# multi-pcb-_base.net
KiCad netlist of a schematic drawn in EAGLE
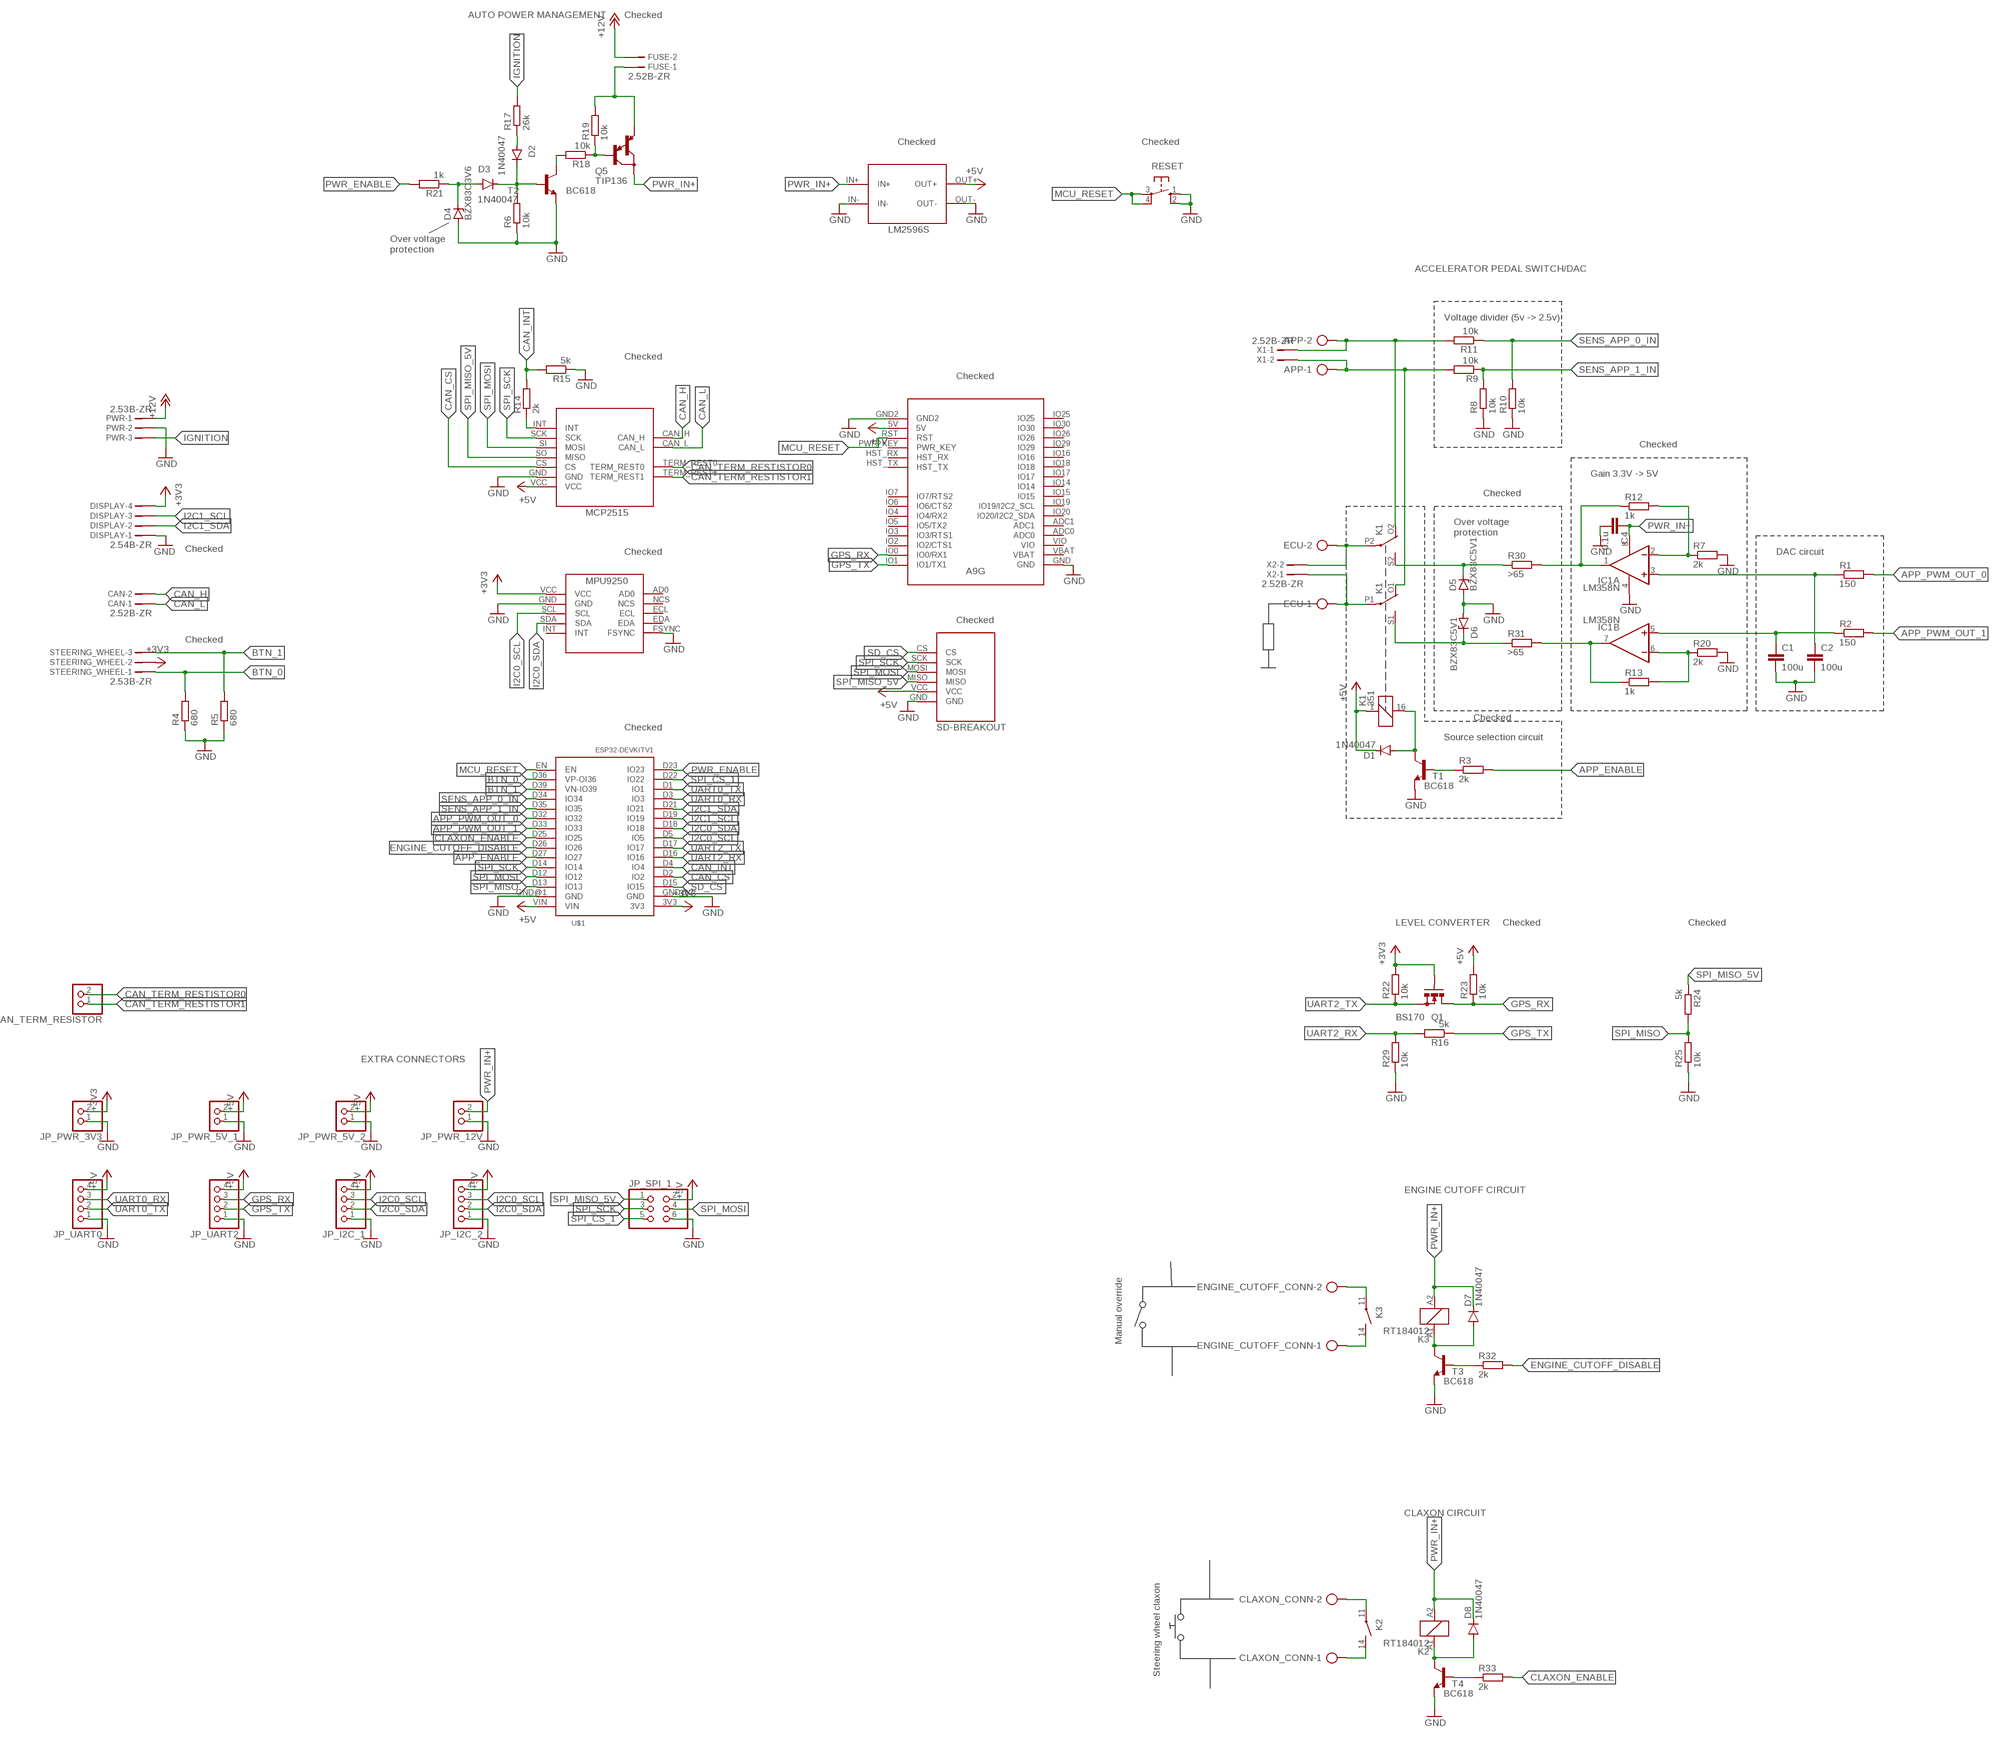
[diagram p0: schematic, sheet 1]

(export (version "E")
  (design (tool "Eeschema 10.0.6"))
  (components
    (comp (ref "APP")
      (value "AK300/2")
      (footprint "eagle-import:AK300_2")
      (libsource (lib "eagle-import") (part "AK300/2"))
    )
    (comp (ref "C1")
      (value "100u")
      (footprint "eagle-import:C025-050X050")
      (libsource (lib "eagle-import") (part "C-EU025-050X050"))
    )
    (comp (ref "C2")
      (value "100u")
      (footprint "eagle-import:C025-050X050")
      (libsource (lib "eagle-import") (part "C-EU025-050X050"))
    )
    (comp (ref "C4")
      (value "0.1u")
      (footprint "eagle-import:C025-050X050")
      (libsource (lib "eagle-import") (part "C-EU025-050X050"))
    )
    (comp (ref "CAN")
      (value "2.52B-ZR")
      (footprint "eagle-import:B2B-ZR2.5")
      (libsource (lib "eagle-import") (part "?2B-ZR2.5"))
    )
    (comp (ref "CAN_TERM_RESISTOR")
      (value "PINHD-1X2")
      (footprint "eagle-import:1X02")
      (libsource (lib "eagle-import") (part "PINHD-1X2"))
    )
    (comp (ref "CLAXON_CONN")
      (value "AK300/2")
      (footprint "eagle-import:AK300_2")
      (libsource (lib "eagle-import") (part "AK300/2"))
    )
    (comp (ref "D1")
      (value "1N40047")
      (footprint "eagle-import:DO41-7.6")
      (libsource (lib "eagle-import") (part "1N40047"))
    )
    (comp (ref "D2")
      (value "1N40047")
      (footprint "eagle-import:DO41-7.6")
      (libsource (lib "eagle-import") (part "1N40047"))
    )
    (comp (ref "D3")
      (value "1N40047")
      (footprint "eagle-import:DO41-7.6")
      (libsource (lib "eagle-import") (part "1N40047"))
    )
    (comp (ref "D4")
      (value "BZX83C3V6")
      (footprint "eagle-import:DO41Z7.6")
      (libsource (lib "eagle-import") (part "BZX857"))
    )
    (comp (ref "D5")
      (value "BZX83C5V1")
      (footprint "eagle-import:DO41Z7.6")
      (libsource (lib "eagle-import") (part "BZX857"))
    )
    (comp (ref "D6")
      (value "BZX83C5V1")
      (footprint "eagle-import:DO41Z7.6")
      (libsource (lib "eagle-import") (part "BZX857"))
    )
    (comp (ref "D7")
      (value "1N40047")
      (footprint "eagle-import:DO41-7.6")
      (libsource (lib "eagle-import") (part "1N40047"))
    )
    (comp (ref "D8")
      (value "1N40047")
      (footprint "eagle-import:DO41-7.6")
      (libsource (lib "eagle-import") (part "1N40047"))
    )
    (comp (ref "DISPLAY")
      (value "2.54B-ZR")
      (footprint "eagle-import:B4B-ZR2.5")
      (libsource (lib "eagle-import") (part "?4B-ZR2.5"))
    )
    (comp (ref "ECU")
      (value "AK300/2")
      (footprint "eagle-import:AK300_2")
      (libsource (lib "eagle-import") (part "AK300/2"))
    )
    (comp (ref "ENGINE_CUTOFF_CONN")
      (value "AK300/2")
      (footprint "eagle-import:AK300_2")
      (libsource (lib "eagle-import") (part "AK300/2"))
    )
    (comp (ref "FUSE")
      (value "2.52B-ZR")
      (footprint "eagle-import:B2B-ZR2.5")
      (libsource (lib "eagle-import") (part "?2B-ZR2.5"))
    )
    (comp (ref "IC1")
      (value "LM358N")
      (footprint "eagle-import:DIL08")
      (libsource (lib "eagle-import") (part "LM358N"))
    )
    (comp (ref "JP_I2C_1")
      (value "PINHD-1X4")
      (footprint "eagle-import:1X04")
      (libsource (lib "eagle-import") (part "PINHD-1X4"))
    )
    (comp (ref "JP_I2C_2")
      (value "PINHD-1X4")
      (footprint "eagle-import:1X04")
      (libsource (lib "eagle-import") (part "PINHD-1X4"))
    )
    (comp (ref "JP_PWR_3V3")
      (value "PINHD-1X2")
      (footprint "eagle-import:1X02")
      (libsource (lib "eagle-import") (part "PINHD-1X2"))
    )
    (comp (ref "JP_PWR_5V_1")
      (value "PINHD-1X2")
      (footprint "eagle-import:1X02")
      (libsource (lib "eagle-import") (part "PINHD-1X2"))
    )
    (comp (ref "JP_PWR_5V_2")
      (value "PINHD-1X2")
      (footprint "eagle-import:1X02")
      (libsource (lib "eagle-import") (part "PINHD-1X2"))
    )
    (comp (ref "JP_PWR_12V")
      (value "PINHD-1X2")
      (footprint "eagle-import:1X02")
      (libsource (lib "eagle-import") (part "PINHD-1X2"))
    )
    (comp (ref "JP_SPI_1")
      (value "PINHD-2X3")
      (footprint "eagle-import:2X03")
      (libsource (lib "eagle-import") (part "PINHD-2X3"))
    )
    (comp (ref "JP_UART0")
      (value "PINHD-1X4")
      (footprint "eagle-import:1X04")
      (libsource (lib "eagle-import") (part "PINHD-1X4"))
    )
    (comp (ref "JP_UART2")
      (value "PINHD-1X4")
      (footprint "eagle-import:1X04")
      (libsource (lib "eagle-import") (part "PINHD-1X4"))
    )
    (comp (ref "K1")
      (value "351")
      (footprint "eagle-import:351")
      (libsource (lib "eagle-import") (part "351"))
    )
    (comp (ref "K2")
      (value "RT184012")
      (footprint "eagle-import:RT-N_O12A3.5")
      (fields (field (name "MF") "TYCO ELECTRONICS"))
      (libsource (lib "eagle-import") (part "RT?184012"))
    )
    (comp (ref "K3")
      (value "RT184012")
      (footprint "eagle-import:RT-N_O12A3.5")
      (fields (field (name "MF") "TYCO ELECTRONICS"))
      (libsource (lib "eagle-import") (part "RT?184012"))
    )
    (comp (ref "PWR")
      (value "2.53B-ZR")
      (footprint "eagle-import:B3B-ZR2.5")
      (libsource (lib "eagle-import") (part "?3B-ZR2.5"))
    )
    (comp (ref "Q1")
      (value "BS170")
      (footprint "eagle-import:SOT54E")
      (libsource (lib "eagle-import") (part "BS170"))
    )
    (comp (ref "Q5")
      (value "TIP136")
      (footprint "eagle-import:TO220")
      (libsource (lib "eagle-import") (part "TIP136"))
    )
    (comp (ref "R1")
      (value "150")
      (footprint "eagle-import:0309_10")
      (libsource (lib "eagle-import") (part "R-EU_0309/10"))
    )
    (comp (ref "R2")
      (value "150")
      (footprint "eagle-import:0309_10")
      (libsource (lib "eagle-import") (part "R-EU_0309/10"))
    )
    (comp (ref "R3")
      (value "2k")
      (footprint "eagle-import:0207_7")
      (libsource (lib "eagle-import") (part "R-EU_0207/7"))
    )
    (comp (ref "R4")
      (value "680")
      (footprint "eagle-import:0207_7")
      (libsource (lib "eagle-import") (part "R-EU_0207/7"))
    )
    (comp (ref "R5")
      (value "680")
      (footprint "eagle-import:0207_7")
      (libsource (lib "eagle-import") (part "R-EU_0207/7"))
    )
    (comp (ref "R6")
      (value "10k")
      (footprint "eagle-import:0207_7")
      (libsource (lib "eagle-import") (part "R-EU_0207/7"))
    )
    (comp (ref "R7")
      (value "2k")
      (footprint "eagle-import:0207_7")
      (libsource (lib "eagle-import") (part "R-EU_0207/7"))
    )
    (comp (ref "R8")
      (value "10k")
      (footprint "eagle-import:0207_7")
      (libsource (lib "eagle-import") (part "R-EU_0207/7"))
    )
    (comp (ref "R9")
      (value "10k")
      (footprint "eagle-import:0309_10")
      (libsource (lib "eagle-import") (part "R-EU_0309/10"))
    )
    (comp (ref "R10")
      (value "10k")
      (footprint "eagle-import:0207_7")
      (libsource (lib "eagle-import") (part "R-EU_0207/7"))
    )
    (comp (ref "R11")
      (value "10k")
      (footprint "eagle-import:0309_10")
      (libsource (lib "eagle-import") (part "R-EU_0309/10"))
    )
    (comp (ref "R12")
      (value "1k")
      (footprint "eagle-import:0207_7")
      (libsource (lib "eagle-import") (part "R-EU_0207/7"))
    )
    (comp (ref "R13")
      (value "1k")
      (footprint "eagle-import:0207_7")
      (libsource (lib "eagle-import") (part "R-EU_0207/7"))
    )
    (comp (ref "R14")
      (value "2k")
      (footprint "eagle-import:0309_10")
      (libsource (lib "eagle-import") (part "R-EU_0309/10"))
    )
    (comp (ref "R15")
      (value "5k")
      (footprint "eagle-import:0207_7")
      (libsource (lib "eagle-import") (part "R-EU_0207/7"))
    )
    (comp (ref "R16")
      (value "5k")
      (footprint "eagle-import:0207_7")
      (libsource (lib "eagle-import") (part "R-EU_0207/7"))
    )
    (comp (ref "R17")
      (value "26k")
      (footprint "eagle-import:0207_7")
      (libsource (lib "eagle-import") (part "R-EU_0207/7"))
    )
    (comp (ref "R18")
      (value "10k")
      (footprint "eagle-import:0207_7")
      (libsource (lib "eagle-import") (part "R-EU_0207/7"))
    )
    (comp (ref "R19")
      (value "10k")
      (footprint "eagle-import:0207_7")
      (libsource (lib "eagle-import") (part "R-EU_0207/7"))
    )
    (comp (ref "R20")
      (value "2k")
      (footprint "eagle-import:0207_7")
      (libsource (lib "eagle-import") (part "R-EU_0207/7"))
    )
    (comp (ref "R21")
      (value "1k")
      (footprint "eagle-import:0309_10")
      (libsource (lib "eagle-import") (part "R-EU_0309/10"))
    )
    (comp (ref "R22")
      (value "10k")
      (footprint "eagle-import:0207_7")
      (libsource (lib "eagle-import") (part "R-EU_0207/7"))
    )
    (comp (ref "R23")
      (value "10k")
      (footprint "eagle-import:0207_7")
      (libsource (lib "eagle-import") (part "R-EU_0207/7"))
    )
    (comp (ref "R24")
      (value "5k")
      (footprint "eagle-import:0207_7")
      (libsource (lib "eagle-import") (part "R-EU_0207/7"))
    )
    (comp (ref "R25")
      (value "10k")
      (footprint "eagle-import:0207_7")
      (libsource (lib "eagle-import") (part "R-EU_0207/7"))
    )
    (comp (ref "R29")
      (value "10k")
      (footprint "eagle-import:0207_7")
      (libsource (lib "eagle-import") (part "R-EU_0207/7"))
    )
    (comp (ref "R30")
      (value ">65")
      (footprint "eagle-import:0207_7")
      (libsource (lib "eagle-import") (part "R-EU_0207/7"))
    )
    (comp (ref "R31")
      (value ">65")
      (footprint "eagle-import:0207_7")
      (libsource (lib "eagle-import") (part "R-EU_0207/7"))
    )
    (comp (ref "R32")
      (value "2k")
      (footprint "eagle-import:0309_10")
      (libsource (lib "eagle-import") (part "R-EU_0309/10"))
    )
    (comp (ref "R33")
      (value "2k")
      (footprint "eagle-import:0309_10")
      (libsource (lib "eagle-import") (part "R-EU_0309/10"))
    )
    (comp (ref "RESET")
      (value "10-XX")
      (footprint "eagle-import:B3F-10XX")
      (fields (field (name "MPN") "B3F-1000"))
      (libsource (lib "eagle-import") (part "10-XX"))
    )
    (comp (ref "STEERING_WHEEL")
      (value "2.53B-ZR")
      (footprint "eagle-import:B3B-ZR2.5")
      (libsource (lib "eagle-import") (part "?3B-ZR2.5"))
    )
    (comp (ref "T1")
      (value "BC618")
      (footprint "eagle-import:TO92-EBC")
      (libsource (lib "eagle-import") (part "BC618"))
    )
    (comp (ref "T2")
      (value "BC618")
      (footprint "eagle-import:TO92-EBC")
      (libsource (lib "eagle-import") (part "BC618"))
    )
    (comp (ref "T3")
      (value "BC618")
      (footprint "eagle-import:TO92-EBC")
      (libsource (lib "eagle-import") (part "BC618"))
    )
    (comp (ref "T4")
      (value "BC618")
      (footprint "eagle-import:TO92-EBC")
      (libsource (lib "eagle-import") (part "BC618"))
    )
    (comp (ref "U$1")
      (value "ESP32DEVKITV1")
      (footprint "eagle-import:ESP32-DEVKITV1")
      (libsource (lib "eagle-import") (part "ESP32DEVKITV1"))
    )
    (comp (ref "U$2")
      (value "MCP2515_DEVBOARDINVERTED")
      (footprint "eagle-import:MCP2515_DEVBOARD_INVERTED")
      (libsource (lib "eagle-import") (part "MCP2515_DEVBOARDINVERTED"))
    )
    (comp (ref "U$3")
      (value "MPU9250_BREAKOUT")
      (footprint "eagle-import:MPU9250_BREAKOUT")
      (libsource (lib "eagle-import") (part "MPU9250_BREAKOUT"))
    )
    (comp (ref "U$4")
      (value "LM2596S")
      (footprint "eagle-import:LM2596S")
      (libsource (lib "eagle-import") (part "LM2596S"))
    )
    (comp (ref "U$5")
      (value "HKD-MICRO-SD-BREAKOUTH")
      (footprint "eagle-import:HKD-MICRO-SD-BREAKOUT")
      (libsource (lib "eagle-import") (part "HKD-MICRO-SD-BREAKOUTH"))
    )
    (comp (ref "U$6")
      (value "A9G")
      (footprint "eagle-import:A9G")
      (libsource (lib "eagle-import") (part "A9G"))
    )
    (comp (ref "X1")
      (value "2.52B-ZR")
      (footprint "eagle-import:B2B-ZR2.5")
      (libsource (lib "eagle-import") (part "?2B-ZR2.5"))
    )
    (comp (ref "X2")
      (value "2.52B-ZR")
      (footprint "eagle-import:B2B-ZR2.5")
      (libsource (lib "eagle-import") (part "?2B-ZR2.5"))
    )
  )
  (nets
    (net (code "1") (name "+3V3") (class "Default")
      (node (ref "DISPLAY") (pin "4") (pinfunction "1_4") (pintype "passive"))
      (node (ref "JP_PWR_3V3") (pin "2") (pinfunction "2_2") (pintype "passive"))
      (node (ref "Q1") (pin "G") (pinfunction "G_G") (pintype "passive"))
      (node (ref "R22") (pin "2") (pinfunction "2_2") (pintype "passive"))
      (node (ref "STEERING_WHEEL") (pin "2") (pinfunction "1_2") (pintype "passive"))
      (node (ref "U$1") (pin "3V3") (pinfunction "3V3_3V3") (pintype "bidirectional"))
      (node (ref "U$3") (pin "VCC") (pinfunction "VCC_VCC") (pintype "bidirectional"))
    )
    (net (code "2") (name "+5V") (class "Default")
      (node (ref "D1") (pin "C") (pinfunction "C_C") (pintype "passive"))
      (node (ref "JP_I2C_1") (pin "4") (pinfunction "4_4") (pintype "passive"))
      (node (ref "JP_I2C_2") (pin "4") (pinfunction "4_4") (pintype "passive"))
      (node (ref "JP_PWR_5V_1") (pin "2") (pinfunction "2_2") (pintype "passive"))
      (node (ref "JP_PWR_5V_2") (pin "2") (pinfunction "2_2") (pintype "passive"))
      (node (ref "JP_SPI_1") (pin "2") (pinfunction "2_2") (pintype "passive"))
      (node (ref "JP_UART0") (pin "4") (pinfunction "4_4") (pintype "passive"))
      (node (ref "JP_UART2") (pin "4") (pinfunction "4_4") (pintype "passive"))
      (node (ref "K1") (pin "1") (pinfunction "1_1") (pintype "passive"))
      (node (ref "R23") (pin "2") (pinfunction "2_2") (pintype "passive"))
      (node (ref "U$1") (pin "VIN") (pinfunction "VIN_VIN") (pintype "bidirectional"))
      (node (ref "U$2") (pin "VCC") (pinfunction "VCC_VCC") (pintype "bidirectional"))
      (node (ref "U$4") (pin "OUT+") (pinfunction "OUT+_OUT+") (pintype "bidirectional"))
      (node (ref "U$5") (pin "VCC") (pinfunction "VCC_VCC") (pintype "bidirectional"))
      (node (ref "U$6") (pin "5V") (pinfunction "5V_5V") (pintype "bidirectional"))
    )
    (net (code "3") (name "+12V") (class "Default")
      (node (ref "FUSE") (pin "2") (pinfunction "1_2") (pintype "passive"))
      (node (ref "PWR") (pin "1") (pinfunction "1_1") (pintype "passive"))
    )
    (net (code "4") (name "APP_ENABLE") (class "Default")
      (node (ref "R3") (pin "2") (pinfunction "2_2") (pintype "passive"))
      (node (ref "U$1") (pin "D27") (pinfunction "IO27_D27") (pintype "bidirectional"))
    )
    (net (code "5") (name "APP_PWM_OUT_0") (class "Default")
      (node (ref "R1") (pin "2") (pinfunction "2_2") (pintype "passive"))
      (node (ref "U$1") (pin "D32") (pinfunction "IO32_D32") (pintype "bidirectional"))
    )
    (net (code "6") (name "APP_PWM_OUT_1") (class "Default")
      (node (ref "R2") (pin "2") (pinfunction "2_2") (pintype "passive"))
      (node (ref "U$1") (pin "D33") (pinfunction "IO33_D33") (pintype "bidirectional"))
    )
    (net (code "7") (name "BTN_0") (class "Default")
      (node (ref "R4") (pin "2") (pinfunction "2_2") (pintype "passive"))
      (node (ref "STEERING_WHEEL") (pin "1") (pinfunction "1_1") (pintype "passive"))
      (node (ref "U$1") (pin "D36") (pinfunction "VP-OI36_D36") (pintype "bidirectional"))
    )
    (net (code "8") (name "BTN_1") (class "Default")
      (node (ref "R5") (pin "2") (pinfunction "2_2") (pintype "passive"))
      (node (ref "STEERING_WHEEL") (pin "3") (pinfunction "1_3") (pintype "passive"))
      (node (ref "U$1") (pin "D39") (pinfunction "VN-IO39_D39") (pintype "bidirectional"))
    )
    (net (code "9") (name "CAN_CS") (class "Default")
      (node (ref "U$1") (pin "D2") (pinfunction "IO2_D2") (pintype "bidirectional"))
      (node (ref "U$2") (pin "CS") (pinfunction "CS_CS") (pintype "input"))
    )
    (net (code "10") (name "CAN_H") (class "Default")
      (node (ref "CAN") (pin "2") (pinfunction "1_2") (pintype "passive"))
      (node (ref "U$2") (pin "CAN_H") (pinfunction "CAN_H_CAN_H") (pintype "bidirectional"))
    )
    (net (code "11") (name "CAN_INT") (class "Default")
      (node (ref "R14") (pin "2") (pinfunction "2_2") (pintype "passive"))
      (node (ref "R15") (pin "2") (pinfunction "2_2") (pintype "passive"))
      (node (ref "U$1") (pin "D4") (pinfunction "IO4_D4") (pintype "bidirectional"))
    )
    (net (code "12") (name "CAN_L") (class "Default")
      (node (ref "CAN") (pin "1") (pinfunction "1_1") (pintype "passive"))
      (node (ref "U$2") (pin "CAN_L") (pinfunction "CAN_L_CAN_L") (pintype "bidirectional"))
    )
    (net (code "13") (name "CAN_TERM_RESTISTOR0") (class "Default")
      (node (ref "CAN_TERM_RESISTOR") (pin "2") (pinfunction "2_2") (pintype "passive"))
      (node (ref "U$2") (pin "TERM_REST0") (pinfunction "TERM_REST0_TERM_REST0") (pintype "bidirectional"))
    )
    (net (code "14") (name "CAN_TERM_RESTISTOR1") (class "Default")
      (node (ref "CAN_TERM_RESISTOR") (pin "1") (pinfunction "1_1") (pintype "passive"))
      (node (ref "U$2") (pin "TERM_REST1") (pinfunction "TERM_REST1_TERM_REST1") (pintype "bidirectional"))
    )
    (net (code "15") (name "CLAXON_ENABLE") (class "Default")
      (node (ref "R33") (pin "2") (pinfunction "2_2") (pintype "passive"))
      (node (ref "U$1") (pin "D25") (pinfunction "IO25_D25") (pintype "bidirectional"))
    )
    (net (code "16") (name "ENGINE_CUTOFF_DISABLE") (class "Default")
      (node (ref "R32") (pin "2") (pinfunction "2_2") (pintype "passive"))
      (node (ref "U$1") (pin "D26") (pinfunction "IO26_D26") (pintype "bidirectional"))
    )
    (net (code "17") (name "GND") (class "Default")
      (node (ref "C1") (pin "2") (pinfunction "2_2") (pintype "passive"))
      (node (ref "C2") (pin "2") (pinfunction "2_2") (pintype "passive"))
      (node (ref "C4") (pin "2") (pinfunction "2_2") (pintype "passive"))
      (node (ref "D4") (pin "A") (pinfunction "A_A") (pintype "passive"))
      (node (ref "D5") (pin "A") (pinfunction "A_A") (pintype "passive"))
      (node (ref "D6") (pin "A") (pinfunction "A_A") (pintype "passive"))
      (node (ref "DISPLAY") (pin "1") (pinfunction "1_1") (pintype "passive"))
      (node (ref "IC1") (pin "4") (pinfunction "V-_4") (pintype "power_in"))
      (node (ref "JP_I2C_1") (pin "1") (pinfunction "1_1") (pintype "passive"))
      (node (ref "JP_I2C_2") (pin "1") (pinfunction "1_1") (pintype "passive"))
      (node (ref "JP_PWR_12V") (pin "1") (pinfunction "1_1") (pintype "passive"))
      (node (ref "JP_PWR_3V3") (pin "1") (pinfunction "1_1") (pintype "passive"))
      (node (ref "JP_PWR_5V_1") (pin "1") (pinfunction "1_1") (pintype "passive"))
      (node (ref "JP_PWR_5V_2") (pin "1") (pinfunction "1_1") (pintype "passive"))
      (node (ref "JP_SPI_1") (pin "6") (pinfunction "6_6") (pintype "passive"))
      (node (ref "JP_UART0") (pin "1") (pinfunction "1_1") (pintype "passive"))
      (node (ref "JP_UART2") (pin "1") (pinfunction "1_1") (pintype "passive"))
      (node (ref "PWR") (pin "2") (pinfunction "1_2") (pintype "passive"))
      (node (ref "R10") (pin "1") (pinfunction "1_1") (pintype "passive"))
      (node (ref "R15") (pin "1") (pinfunction "1_1") (pintype "passive"))
      (node (ref "R20") (pin "2") (pinfunction "2_2") (pintype "passive"))
      (node (ref "R25") (pin "1") (pinfunction "1_1") (pintype "passive"))
      (node (ref "R29") (pin "1") (pinfunction "1_1") (pintype "passive"))
      (node (ref "R4") (pin "1") (pinfunction "1_1") (pintype "passive"))
      (node (ref "R5") (pin "1") (pinfunction "1_1") (pintype "passive"))
      (node (ref "R6") (pin "1") (pinfunction "1_1") (pintype "passive"))
      (node (ref "R7") (pin "2") (pinfunction "2_2") (pintype "passive"))
      (node (ref "R8") (pin "1") (pinfunction "1_1") (pintype "passive"))
      (node (ref "RESET") (pin "1") (pinfunction "S_1") (pintype "passive"))
      (node (ref "RESET") (pin "2") (pinfunction "S1_2") (pintype "passive"))
      (node (ref "T1") (pin "E") (pinfunction "E_E") (pintype "passive"))
      (node (ref "T2") (pin "E") (pinfunction "E_E") (pintype "passive"))
      (node (ref "T3") (pin "E") (pinfunction "E_E") (pintype "passive"))
      (node (ref "T4") (pin "E") (pinfunction "E_E") (pintype "passive"))
      (node (ref "U$1") (pin "GND@1") (pinfunction "GND_GND@1") (pintype "bidirectional"))
      (node (ref "U$1") (pin "GND@2") (pinfunction "GND_GND@2") (pintype "bidirectional"))
      (node (ref "U$2") (pin "GND") (pinfunction "GND_GND") (pintype "bidirectional"))
      (node (ref "U$3") (pin "FSYNC") (pinfunction "FSYNC_FSYNC") (pintype "bidirectional"))
      (node (ref "U$3") (pin "GND") (pinfunction "GND_GND") (pintype "bidirectional"))
      (node (ref "U$4") (pin "IN-") (pinfunction "IN-_IN-") (pintype "bidirectional"))
      (node (ref "U$4") (pin "OUT-") (pinfunction "OUT-_OUT-") (pintype "bidirectional"))
      (node (ref "U$5") (pin "GND") (pinfunction "GND_GND") (pintype "bidirectional"))
      (node (ref "U$6") (pin "GND") (pinfunction "GND_GND") (pintype "bidirectional"))
      (node (ref "U$6") (pin "GND2") (pinfunction "GND2_GND2") (pintype "bidirectional"))
    )
    (net (code "18") (name "GPS_RX") (class "Default")
      (node (ref "JP_UART2") (pin "3") (pinfunction "3_3") (pintype "passive"))
      (node (ref "Q1") (pin "D") (pinfunction "D_D") (pintype "passive"))
      (node (ref "R23") (pin "1") (pinfunction "1_1") (pintype "passive"))
      (node (ref "U$6") (pin "IO0") (pinfunction "IO0/RX1_IO0") (pintype "bidirectional"))
    )
    (net (code "19") (name "GPS_TX") (class "Default")
      (node (ref "JP_UART2") (pin "2") (pinfunction "2_2") (pintype "passive"))
      (node (ref "R16") (pin "1") (pinfunction "1_1") (pintype "passive"))
      (node (ref "U$6") (pin "IO1") (pinfunction "IO1/TX1_IO1") (pintype "bidirectional"))
    )
    (net (code "20") (name "I2C0_SCL") (class "Default")
      (node (ref "JP_I2C_1") (pin "3") (pinfunction "3_3") (pintype "passive"))
      (node (ref "JP_I2C_2") (pin "3") (pinfunction "3_3") (pintype "passive"))
      (node (ref "U$1") (pin "D5") (pinfunction "IO5_D5") (pintype "bidirectional"))
      (node (ref "U$3") (pin "SCL") (pinfunction "SCL_SCL") (pintype "bidirectional"))
    )
    (net (code "21") (name "I2C0_SDA") (class "Default")
      (node (ref "JP_I2C_1") (pin "2") (pinfunction "2_2") (pintype "passive"))
      (node (ref "JP_I2C_2") (pin "2") (pinfunction "2_2") (pintype "passive"))
      (node (ref "U$1") (pin "D18") (pinfunction "IO18_D18") (pintype "bidirectional"))
      (node (ref "U$3") (pin "SDA") (pinfunction "SDA_SDA") (pintype "bidirectional"))
    )
    (net (code "22") (name "I2C1_SCL") (class "Default")
      (node (ref "DISPLAY") (pin "3") (pinfunction "1_3") (pintype "passive"))
      (node (ref "U$1") (pin "D19") (pinfunction "IO19_D19") (pintype "bidirectional"))
    )
    (net (code "23") (name "I2C1_SDA") (class "Default")
      (node (ref "DISPLAY") (pin "2") (pinfunction "1_2") (pintype "passive"))
      (node (ref "U$1") (pin "D21") (pinfunction "IO21_D21") (pintype "bidirectional"))
    )
    (net (code "24") (name "IGNITION") (class "Default")
      (node (ref "PWR") (pin "3") (pinfunction "1_3") (pintype "passive"))
      (node (ref "R17") (pin "2") (pinfunction "2_2") (pintype "passive"))
    )
    (net (code "25") (name "MCU_RESET") (class "Default")
      (node (ref "RESET") (pin "3") (pinfunction "P_3") (pintype "passive"))
      (node (ref "RESET") (pin "4") (pinfunction "P1_4") (pintype "passive"))
      (node (ref "U$1") (pin "EN") (pinfunction "EN_EN") (pintype "bidirectional"))
      (node (ref "U$6") (pin "RST") (pinfunction "RST_RST") (pintype "bidirectional"))
    )
    (net (code "26") (name "Net-(APPA-KL)") (class "Default")
      (node (ref "APP") (pin "1") (pinfunction "KL_1") (pintype "passive"))
      (node (ref "K1") (pin "O1") (pinfunction "O_O1") (pintype "passive"))
      (node (ref "R9") (pin "2") (pinfunction "2_2") (pintype "passive"))
      (node (ref "X1") (pin "2") (pinfunction "1_2") (pintype "passive"))
    )
    (net (code "27") (name "Net-(APPB-KL)") (class "Default")
      (node (ref "APP") (pin "2") (pinfunction "KL_2") (pintype "passive"))
      (node (ref "K1") (pin "O2") (pinfunction "O_O2") (pintype "passive"))
      (node (ref "R11") (pin "2") (pinfunction "2_2") (pintype "passive"))
      (node (ref "X1") (pin "1") (pinfunction "1_1") (pintype "passive"))
    )
    (net (code "28") (name "Net-(CLAXON_CONNA-KL)") (class "Default")
      (node (ref "CLAXON_CONN") (pin "1") (pinfunction "KL_1") (pintype "passive"))
      (node (ref "K2") (pin "14") (pinfunction "S_14") (pintype "passive"))
    )
    (net (code "29") (name "Net-(CLAXON_CONNB-KL)") (class "Default")
      (node (ref "CLAXON_CONN") (pin "2") (pinfunction "KL_2") (pintype "passive"))
      (node (ref "K2") (pin "11") (pinfunction "P_11") (pintype "passive"))
    )
    (net (code "30") (name "Net-(D2-PadA)") (class "Default")
      (node (ref "D2") (pin "A") (pinfunction "A_A") (pintype "passive"))
      (node (ref "R17") (pin "1") (pinfunction "1_1") (pintype "passive"))
    )
    (net (code "31") (name "Net-(D2-PadC)") (class "Default")
      (node (ref "D2") (pin "C") (pinfunction "C_C") (pintype "passive"))
      (node (ref "D3") (pin "C") (pinfunction "C_C") (pintype "passive"))
      (node (ref "R6") (pin "2") (pinfunction "2_2") (pintype "passive"))
      (node (ref "T2") (pin "B") (pinfunction "B_B") (pintype "passive"))
    )
    (net (code "32") (name "Net-(D3-PadA)") (class "Default")
      (node (ref "D3") (pin "A") (pinfunction "A_A") (pintype "passive"))
      (node (ref "D4") (pin "C") (pinfunction "C_C") (pintype "passive"))
      (node (ref "R21") (pin "1") (pinfunction "1_1") (pintype "passive"))
    )
    (net (code "33") (name "Net-(ECUA-KL)") (class "Default")
      (node (ref "ECU") (pin "1") (pinfunction "KL_1") (pintype "passive"))
      (node (ref "K1") (pin "P1") (pinfunction "P_P1") (pintype "passive"))
      (node (ref "X2") (pin "1") (pinfunction "1_1") (pintype "passive"))
    )
    (net (code "34") (name "Net-(ECUB-KL)") (class "Default")
      (node (ref "ECU") (pin "2") (pinfunction "KL_2") (pintype "passive"))
      (node (ref "K1") (pin "P2") (pinfunction "P_P2") (pintype "passive"))
      (node (ref "X2") (pin "2") (pinfunction "1_2") (pintype "passive"))
    )
    (net (code "35") (name "Net-(ENGINE_CUTOFF_CONNA-KL)") (class "Default")
      (node (ref "ENGINE_CUTOFF_CONN") (pin "1") (pinfunction "KL_1") (pintype "passive"))
      (node (ref "K3") (pin "14") (pinfunction "S_14") (pintype "passive"))
    )
    (net (code "36") (name "Net-(ENGINE_CUTOFF_CONNB-KL)") (class "Default")
      (node (ref "ENGINE_CUTOFF_CONN") (pin "2") (pinfunction "KL_2") (pintype "passive"))
      (node (ref "K3") (pin "11") (pinfunction "P_11") (pintype "passive"))
    )
    (net (code "37") (name "Net-(IC1A-+IN)") (class "Default")
      (node (ref "C2") (pin "1") (pinfunction "1_1") (pintype "passive"))
      (node (ref "IC1") (pin "3") (pinfunction "+IN_3") (pintype "input"))
      (node (ref "R1") (pin "1") (pinfunction "1_1") (pintype "passive"))
    )
    (net (code "38") (name "Net-(IC1A--IN)") (class "Default")
      (node (ref "IC1") (pin "2") (pinfunction "-IN_2") (pintype "input"))
      (node (ref "R12") (pin "2") (pinfunction "2_2") (pintype "passive"))
      (node (ref "R7") (pin "1") (pinfunction "1_1") (pintype "passive"))
    )
    (net (code "39") (name "Net-(IC1A-OUT)") (class "Default")
      (node (ref "IC1") (pin "1") (pinfunction "OUT_1") (pintype "output"))
      (node (ref "R12") (pin "1") (pinfunction "1_1") (pintype "passive"))
      (node (ref "R30") (pin "2") (pinfunction "2_2") (pintype "passive"))
    )
    (net (code "40") (name "Net-(IC1B-+IN)") (class "Default")
      (node (ref "C1") (pin "1") (pinfunction "1_1") (pintype "passive"))
      (node (ref "IC1") (pin "5") (pinfunction "+IN_5") (pintype "input"))
      (node (ref "R2") (pin "1") (pinfunction "1_1") (pintype "passive"))
    )
    (net (code "41") (name "Net-(IC1B--IN)") (class "Default")
      (node (ref "IC1") (pin "6") (pinfunction "-IN_6") (pintype "input"))
      (node (ref "R13") (pin "2") (pinfunction "2_2") (pintype "passive"))
      (node (ref "R20") (pin "1") (pinfunction "1_1") (pintype "passive"))
    )
    (net (code "42") (name "Net-(IC1B-OUT)") (class "Default")
      (node (ref "IC1") (pin "7") (pinfunction "OUT_7") (pintype "output"))
      (node (ref "R13") (pin "1") (pinfunction "1_1") (pintype "passive"))
      (node (ref "R31") (pin "2") (pinfunction "2_2") (pintype "passive"))
    )
    (net (code "43") (name "Net-(K1A-2)") (class "Default")
      (node (ref "D1") (pin "A") (pinfunction "A_A") (pintype "passive"))
      (node (ref "K1") (pin "16") (pinfunction "2_16") (pintype "passive"))
      (node (ref "T1") (pin "C") (pinfunction "C_C") (pintype "passive"))
    )
    (net (code "44") (name "Net-(K1B-S)") (class "Default")
      (node (ref "D6") (pin "C") (pinfunction "C_C") (pintype "passive"))
      (node (ref "K1") (pin "S1") (pinfunction "S_S1") (pintype "passive"))
      (node (ref "R31") (pin "1") (pinfunction "1_1") (pintype "passive"))
    )
    (net (code "45") (name "Net-(K1C-S)") (class "Default")
      (node (ref "D5") (pin "C") (pinfunction "C_C") (pintype "passive"))
      (node (ref "K1") (pin "S2") (pinfunction "S_S2") (pintype "passive"))
      (node (ref "R30") (pin "1") (pinfunction "1_1") (pintype "passive"))
    )
    (net (code "46") (name "Net-(K2A-1)") (class "Default")
      (node (ref "D8") (pin "A") (pinfunction "A_A") (pintype "passive"))
      (node (ref "K2") (pin "A1") (pinfunction "1_A1") (pintype "passive"))
      (node (ref "T4") (pin "C") (pinfunction "C_C") (pintype "passive"))
    )
    (net (code "47") (name "Net-(K3A-1)") (class "Default")
      (node (ref "D7") (pin "A") (pinfunction "A_A") (pintype "passive"))
      (node (ref "K3") (pin "A1") (pinfunction "1_A1") (pintype "passive"))
      (node (ref "T3") (pin "C") (pinfunction "C_C") (pintype "passive"))
    )
    (net (code "48") (name "Net-(Q5-B)") (class "Default")
      (node (ref "Q5") (pin "1") (pinfunction "B_1") (pintype "passive"))
      (node (ref "R18") (pin "1") (pinfunction "1_1") (pintype "passive"))
      (node (ref "R19") (pin "1") (pinfunction "1_1") (pintype "passive"))
    )
    (net (code "49") (name "Net-(Q5-E)") (class "Default")
      (node (ref "FUSE") (pin "1") (pinfunction "1_1") (pintype "passive"))
      (node (ref "Q5") (pin "3") (pinfunction "E_3") (pintype "passive"))
      (node (ref "R19") (pin "2") (pinfunction "2_2") (pintype "passive"))
    )
    (net (code "50") (name "Net-(R3-Pad1)") (class "Default")
      (node (ref "R3") (pin "1") (pinfunction "1_1") (pintype "passive"))
      (node (ref "T1") (pin "B") (pinfunction "B_B") (pintype "passive"))
    )
    (net (code "51") (name "Net-(R14-Pad1)") (class "Default")
      (node (ref "R14") (pin "1") (pinfunction "1_1") (pintype "passive"))
      (node (ref "U$2") (pin "INT") (pinfunction "INT_INT") (pintype "output"))
    )
    (net (code "52") (name "Net-(R18-Pad2)") (class "Default")
      (node (ref "R18") (pin "2") (pinfunction "2_2") (pintype "passive"))
      (node (ref "T2") (pin "C") (pinfunction "C_C") (pintype "passive"))
    )
    (net (code "53") (name "Net-(R32-Pad1)") (class "Default")
      (node (ref "R32") (pin "1") (pinfunction "1_1") (pintype "passive"))
      (node (ref "T3") (pin "B") (pinfunction "B_B") (pintype "passive"))
    )
    (net (code "54") (name "Net-(R33-Pad1)") (class "Default")
      (node (ref "R33") (pin "1") (pinfunction "1_1") (pintype "passive"))
      (node (ref "T4") (pin "B") (pinfunction "B_B") (pintype "passive"))
    )
    (net (code "55") (name "PWR_ENABLE") (class "Default")
      (node (ref "R21") (pin "2") (pinfunction "2_2") (pintype "passive"))
      (node (ref "U$1") (pin "D23") (pinfunction "IO23_D23") (pintype "bidirectional"))
    )
    (net (code "56") (name "PWR_IN+") (class "Default")
      (node (ref "C4") (pin "1") (pinfunction "1_1") (pintype "passive"))
      (node (ref "D7") (pin "C") (pinfunction "C_C") (pintype "passive"))
      (node (ref "D8") (pin "C") (pinfunction "C_C") (pintype "passive"))
      (node (ref "IC1") (pin "8") (pinfunction "V+_8") (pintype "power_in"))
      (node (ref "JP_PWR_12V") (pin "2") (pinfunction "2_2") (pintype "passive"))
      (node (ref "K2") (pin "A2") (pinfunction "2_A2") (pintype "passive"))
      (node (ref "K3") (pin "A2") (pinfunction "2_A2") (pintype "passive"))
      (node (ref "Q5") (pin "2") (pinfunction "C_2") (pintype "passive"))
      (node (ref "U$4") (pin "IN+") (pinfunction "IN+_IN+") (pintype "bidirectional"))
    )
    (net (code "57") (name "SD_CS") (class "Default")
      (node (ref "U$1") (pin "D15") (pinfunction "IO15_D15") (pintype "bidirectional"))
      (node (ref "U$5") (pin "CS") (pinfunction "CS_CS") (pintype "bidirectional"))
    )
    (net (code "58") (name "SENS_APP_0_IN") (class "Default")
      (node (ref "R10") (pin "2") (pinfunction "2_2") (pintype "passive"))
      (node (ref "R11") (pin "1") (pinfunction "1_1") (pintype "passive"))
      (node (ref "U$1") (pin "D34") (pinfunction "IO34_D34") (pintype "bidirectional"))
    )
    (net (code "59") (name "SENS_APP_1_IN") (class "Default")
      (node (ref "R8") (pin "2") (pinfunction "2_2") (pintype "passive"))
      (node (ref "R9") (pin "1") (pinfunction "1_1") (pintype "passive"))
      (node (ref "U$1") (pin "D35") (pinfunction "IO35_D35") (pintype "bidirectional"))
    )
    (net (code "60") (name "SPI_CS_1") (class "Default")
      (node (ref "JP_SPI_1") (pin "5") (pinfunction "5_5") (pintype "passive"))
      (node (ref "U$1") (pin "D22") (pinfunction "IO22_D22") (pintype "bidirectional"))
    )
    (net (code "61") (name "SPI_MISO") (class "Default")
      (node (ref "R24") (pin "2") (pinfunction "2_2") (pintype "passive"))
      (node (ref "R25") (pin "2") (pinfunction "2_2") (pintype "passive"))
      (node (ref "U$1") (pin "D13") (pinfunction "IO13_D13") (pintype "bidirectional"))
    )
    (net (code "62") (name "SPI_MISO_5V") (class "Default")
      (node (ref "JP_SPI_1") (pin "1") (pinfunction "1_1") (pintype "passive"))
      (node (ref "R24") (pin "1") (pinfunction "1_1") (pintype "passive"))
      (node (ref "U$2") (pin "SO") (pinfunction "MISO_SO") (pintype "output"))
      (node (ref "U$5") (pin "MISO") (pinfunction "MISO_MISO") (pintype "bidirectional"))
    )
    (net (code "63") (name "SPI_MOSI") (class "Default")
      (node (ref "JP_SPI_1") (pin "4") (pinfunction "4_4") (pintype "passive"))
      (node (ref "U$1") (pin "D12") (pinfunction "IO12_D12") (pintype "bidirectional"))
      (node (ref "U$2") (pin "SI") (pinfunction "MOSI_SI") (pintype "input"))
      (node (ref "U$5") (pin "MOSI") (pinfunction "MOSI_MOSI") (pintype "bidirectional"))
    )
    (net (code "64") (name "SPI_SCK") (class "Default")
      (node (ref "JP_SPI_1") (pin "3") (pinfunction "3_3") (pintype "passive"))
      (node (ref "U$1") (pin "D14") (pinfunction "IO14_D14") (pintype "bidirectional"))
      (node (ref "U$2") (pin "SCK") (pinfunction "SCK_SCK") (pintype "input"))
      (node (ref "U$5") (pin "SCK") (pinfunction "SCK_SCK") (pintype "bidirectional"))
    )
    (net (code "65") (name "UART0_RX") (class "Default")
      (node (ref "JP_UART0") (pin "3") (pinfunction "3_3") (pintype "passive"))
      (node (ref "U$1") (pin "D3") (pinfunction "IO3_D3") (pintype "bidirectional"))
    )
    (net (code "66") (name "UART0_TX") (class "Default")
      (node (ref "JP_UART0") (pin "2") (pinfunction "2_2") (pintype "passive"))
      (node (ref "U$1") (pin "D1") (pinfunction "IO1_D1") (pintype "bidirectional"))
    )
    (net (code "67") (name "UART2_RX") (class "Default")
      (node (ref "R16") (pin "2") (pinfunction "2_2") (pintype "passive"))
      (node (ref "R29") (pin "2") (pinfunction "2_2") (pintype "passive"))
      (node (ref "U$1") (pin "D16") (pinfunction "IO16_D16") (pintype "bidirectional"))
    )
    (net (code "68") (name "UART2_TX") (class "Default")
      (node (ref "Q1") (pin "S") (pinfunction "S_S") (pintype "passive"))
      (node (ref "R22") (pin "1") (pinfunction "1_1") (pintype "passive"))
      (node (ref "U$1") (pin "D17") (pinfunction "IO17_D17") (pintype "bidirectional"))
    )
    (net (code "69") (name "unconnected-(U$3-PadAD0)") (class "Default")
      (node (ref "U$3") (pin "AD0") (pinfunction "AD0_AD0") (pintype "bidirectional"))
    )
    (net (code "70") (name "unconnected-(U$3-PadECL)") (class "Default")
      (node (ref "U$3") (pin "ECL") (pinfunction "ECL_ECL") (pintype "bidirectional"))
    )
    (net (code "71") (name "unconnected-(U$3-PadEDA)") (class "Default")
      (node (ref "U$3") (pin "EDA") (pinfunction "EDA_EDA") (pintype "bidirectional"))
    )
    (net (code "72") (name "unconnected-(U$3-PadINT)") (class "Default")
      (node (ref "U$3") (pin "INT") (pinfunction "INT_INT") (pintype "bidirectional"))
    )
    (net (code "73") (name "unconnected-(U$3-PadNCS)") (class "Default")
      (node (ref "U$3") (pin "NCS") (pinfunction "NCS_NCS") (pintype "bidirectional"))
    )
    (net (code "74") (name "unconnected-(U$6-IO2{slash}CTS1-PadIO2)") (class "Default")
      (node (ref "U$6") (pin "IO2") (pinfunction "IO2/CTS1_IO2") (pintype "bidirectional"))
    )
    (net (code "75") (name "unconnected-(U$6-IO3{slash}RTS1-PadIO3)") (class "Default")
      (node (ref "U$6") (pin "IO3") (pinfunction "IO3/RTS1_IO3") (pintype "bidirectional"))
    )
    (net (code "76") (name "unconnected-(U$6-IO4{slash}RX2-PadIO4)") (class "Default")
      (node (ref "U$6") (pin "IO4") (pinfunction "IO4/RX2_IO4") (pintype "bidirectional"))
    )
    (net (code "77") (name "unconnected-(U$6-IO5{slash}TX2-PadIO5)") (class "Default")
      (node (ref "U$6") (pin "IO5") (pinfunction "IO5/TX2_IO5") (pintype "bidirectional"))
    )
    (net (code "78") (name "unconnected-(U$6-IO6{slash}CTS2-PadIO6)") (class "Default")
      (node (ref "U$6") (pin "IO6") (pinfunction "IO6/CTS2_IO6") (pintype "bidirectional"))
    )
    (net (code "79") (name "unconnected-(U$6-IO7{slash}RTS2-PadIO7)") (class "Default")
      (node (ref "U$6") (pin "IO7") (pinfunction "IO7/RTS2_IO7") (pintype "bidirectional"))
    )
    (net (code "80") (name "unconnected-(U$6-IO19{slash}I2C2_SCL-PadIO19)") (class "Default")
      (node (ref "U$6") (pin "IO19") (pinfunction "IO19/I2C2_SCL_IO19") (pintype "bidirectional"))
    )
    (net (code "81") (name "unconnected-(U$6-IO20{slash}I2C2_SDA-PadIO20)") (class "Default")
      (node (ref "U$6") (pin "IO20") (pinfunction "IO20/I2C2_SDA_IO20") (pintype "bidirectional"))
    )
    (net (code "82") (name "unconnected-(U$6-PadADC0)") (class "Default")
      (node (ref "U$6") (pin "ADC0") (pinfunction "ADC0_ADC0") (pintype "bidirectional"))
    )
    (net (code "83") (name "unconnected-(U$6-PadADC1)") (class "Default")
      (node (ref "U$6") (pin "ADC1") (pinfunction "ADC1_ADC1") (pintype "bidirectional"))
    )
    (net (code "84") (name "unconnected-(U$6-PadHST_RX)") (class "Default")
      (node (ref "U$6") (pin "HST_RX") (pinfunction "HST_RX_HST_RX") (pintype "bidirectional"))
    )
    (net (code "85") (name "unconnected-(U$6-PadHST_TX)") (class "Default")
      (node (ref "U$6") (pin "HST_TX") (pinfunction "HST_TX_HST_TX") (pintype "bidirectional"))
    )
    (net (code "86") (name "unconnected-(U$6-PadIO14)") (class "Default")
      (node (ref "U$6") (pin "IO14") (pinfunction "IO14_IO14") (pintype "bidirectional"))
    )
    (net (code "87") (name "unconnected-(U$6-PadIO15)") (class "Default")
      (node (ref "U$6") (pin "IO15") (pinfunction "IO15_IO15") (pintype "bidirectional"))
    )
    (net (code "88") (name "unconnected-(U$6-PadIO16)") (class "Default")
      (node (ref "U$6") (pin "IO16") (pinfunction "IO16_IO16") (pintype "bidirectional"))
    )
    (net (code "89") (name "unconnected-(U$6-PadIO17)") (class "Default")
      (node (ref "U$6") (pin "IO17") (pinfunction "IO17_IO17") (pintype "bidirectional"))
    )
    (net (code "90") (name "unconnected-(U$6-PadIO18)") (class "Default")
      (node (ref "U$6") (pin "IO18") (pinfunction "IO18_IO18") (pintype "bidirectional"))
    )
    (net (code "91") (name "unconnected-(U$6-PadIO25)") (class "Default")
      (node (ref "U$6") (pin "IO25") (pinfunction "IO25_IO25") (pintype "bidirectional"))
    )
    (net (code "92") (name "unconnected-(U$6-PadIO26)") (class "Default")
      (node (ref "U$6") (pin "IO26") (pinfunction "IO26_IO26") (pintype "bidirectional"))
    )
    (net (code "93") (name "unconnected-(U$6-PadIO29)") (class "Default")
      (node (ref "U$6") (pin "IO29") (pinfunction "IO29_IO29") (pintype "bidirectional"))
    )
    (net (code "94") (name "unconnected-(U$6-PadIO30)") (class "Default")
      (node (ref "U$6") (pin "IO30") (pinfunction "IO30_IO30") (pintype "bidirectional"))
    )
    (net (code "95") (name "unconnected-(U$6-PadPWR_KEY)") (class "Default")
      (node (ref "U$6") (pin "PWR_KEY") (pinfunction "PWR_KEY_PWR_KEY") (pintype "bidirectional"))
    )
    (net (code "96") (name "unconnected-(U$6-PadVBAT)") (class "Default")
      (node (ref "U$6") (pin "VBAT") (pinfunction "VBAT_VBAT") (pintype "bidirectional"))
    )
    (net (code "97") (name "unconnected-(U$6-PadVIO)") (class "Default")
      (node (ref "U$6") (pin "VIO") (pinfunction "VIO_VIO") (pintype "bidirectional"))
    )
  )
)
